# Processor.net
KiCad netlist of a schematic drawn in Altium Designer
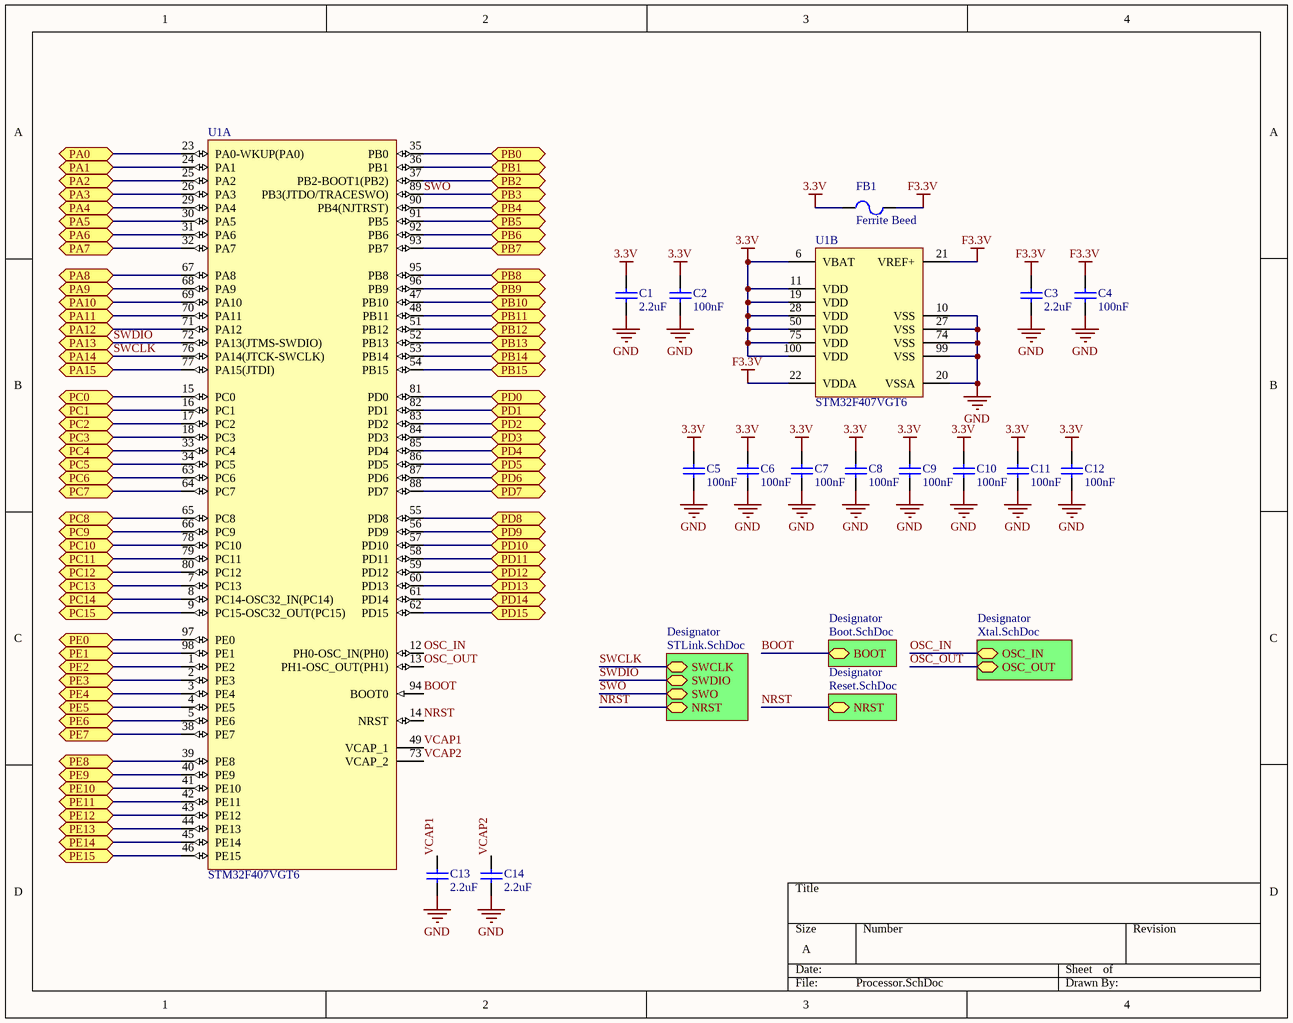
[diagram p0: Processor.SchDoc]

(export (version "E")
  (design (tool "Eeschema 10.0.6"))
  (components
    (comp (ref "C1")
      (value "2.2uF")
      (footprint "2012[0805]")
      (description "Capacitor")
      (fields (field (name "Comment") "Cap_UP") (field (name "PUBLISHER") "Altium Limited"))
      (libsource (lib "KN2CLib") (part "Cap_UP"))
    )
    (comp (ref "C2")
      (value "100nF")
      (footprint "2012[0805]")
      (description "Capacitor")
      (fields (field (name "Comment") "Cap_UP") (field (name "PUBLISHER") "Altium Limited"))
      (libsource (lib "KN2CLib") (part "Cap_UP"))
    )
    (comp (ref "C3")
      (value "2.2uF")
      (footprint "2012[0805]")
      (description "Capacitor")
      (fields (field (name "Comment") "Cap_UP") (field (name "PUBLISHER") "Altium Limited"))
      (libsource (lib "KN2CLib") (part "Cap_UP"))
    )
    (comp (ref "C4")
      (value "100nF")
      (footprint "2012[0805]")
      (description "Capacitor")
      (fields (field (name "Comment") "Cap_UP") (field (name "PUBLISHER") "Altium Limited"))
      (libsource (lib "KN2CLib") (part "Cap_UP"))
    )
    (comp (ref "C5")
      (value "100nF")
      (footprint "2012[0805]")
      (description "Capacitor")
      (fields (field (name "Comment") "Cap_UP") (field (name "PUBLISHER") "Altium Limited"))
      (libsource (lib "KN2CLib") (part "Cap_UP"))
    )
    (comp (ref "C6")
      (value "100nF")
      (footprint "2012[0805]")
      (description "Capacitor")
      (fields (field (name "Comment") "Cap_UP") (field (name "PUBLISHER") "Altium Limited"))
      (libsource (lib "KN2CLib") (part "Cap_UP"))
    )
    (comp (ref "C7")
      (value "100nF")
      (footprint "2012[0805]")
      (description "Capacitor")
      (fields (field (name "Comment") "Cap_UP") (field (name "PUBLISHER") "Altium Limited"))
      (libsource (lib "KN2CLib") (part "Cap_UP"))
    )
    (comp (ref "C8")
      (value "100nF")
      (footprint "2012[0805]")
      (description "Capacitor")
      (fields (field (name "Comment") "Cap_UP") (field (name "PUBLISHER") "Altium Limited"))
      (libsource (lib "KN2CLib") (part "Cap_UP"))
    )
    (comp (ref "C9")
      (value "100nF")
      (footprint "2012[0805]")
      (description "Capacitor")
      (fields (field (name "Comment") "Cap_UP") (field (name "PUBLISHER") "Altium Limited"))
      (libsource (lib "KN2CLib") (part "Cap_UP"))
    )
    (comp (ref "C10")
      (value "100nF")
      (footprint "2012[0805]")
      (description "Capacitor")
      (fields (field (name "Comment") "Cap_UP") (field (name "PUBLISHER") "Altium Limited"))
      (libsource (lib "KN2CLib") (part "Cap_UP"))
    )
    (comp (ref "C11")
      (value "100nF")
      (footprint "2012[0805]")
      (description "Capacitor")
      (fields (field (name "Comment") "Cap_UP") (field (name "PUBLISHER") "Altium Limited"))
      (libsource (lib "KN2CLib") (part "Cap_UP"))
    )
    (comp (ref "C12")
      (value "100nF")
      (footprint "2012[0805]")
      (description "Capacitor")
      (fields (field (name "Comment") "Cap_UP") (field (name "PUBLISHER") "Altium Limited"))
      (libsource (lib "KN2CLib") (part "Cap_UP"))
    )
    (comp (ref "C13")
      (value "2.2uF")
      (footprint "2012[0805]")
      (description "Capacitor")
      (fields (field (name "Comment") "Cap_UP") (field (name "PUBLISHER") "Altium Limited"))
      (libsource (lib "KN2CLib") (part "Cap_UP"))
    )
    (comp (ref "C14")
      (value "2.2uF")
      (footprint "2012[0805]")
      (description "Capacitor")
      (fields (field (name "Comment") "Cap_UP") (field (name "PUBLISHER") "Altium Limited"))
      (libsource (lib "KN2CLib") (part "Cap_UP"))
    )
    (comp (ref "FB1")
      (value "Ferrite Beed")
      (footprint "3216[1206]")
      (fields (field (name "PUBLISHER") "Altium Limited"))
      (libsource (lib "KN2CLib") (part "Ferrite Beed"))
    )
    (comp (ref "U1")
      (value "STM32F407VGT6")
      (footprint "STM-LQFP100_N")
      (fields (field (name "MANUFACTURER") "STMicroelectronics"))
      (libsource (lib "STMicroelectronics STM32 F4") (part "STM32F407VGT6"))
    )
  )
  (nets
    (net (code "1") (name "/BOOT") (class "Default")
      (node (ref "U1") (pin "94") (pinfunction "BOOT0_94") (pintype "input"))
    )
    (net (code "2") (name "/NRST") (class "Default")
      (node (ref "U1") (pin "14") (pinfunction "NRST_14") (pintype "bidirectional"))
    )
    (net (code "3") (name "/OSC_IN") (class "Default")
      (node (ref "U1") (pin "12") (pinfunction "PH0-OSC_IN(PH0)_12") (pintype "bidirectional"))
    )
    (net (code "4") (name "/OSC_OUT") (class "Default")
      (node (ref "U1") (pin "13") (pinfunction "PH1-OSC_OUT(PH1)_13") (pintype "bidirectional"))
    )
    (net (code "5") (name "/PA0") (class "Default")
      (node (ref "U1") (pin "23") (pinfunction "PA0-WKUP(PA0)_23") (pintype "bidirectional"))
    )
    (net (code "6") (name "/PA1") (class "Default")
      (node (ref "U1") (pin "24") (pinfunction "PA1_24") (pintype "bidirectional"))
    )
    (net (code "7") (name "/PA2") (class "Default")
      (node (ref "U1") (pin "25") (pinfunction "PA2_25") (pintype "bidirectional"))
    )
    (net (code "8") (name "/PA3") (class "Default")
      (node (ref "U1") (pin "26") (pinfunction "PA3_26") (pintype "bidirectional"))
    )
    (net (code "9") (name "/PA4") (class "Default")
      (node (ref "U1") (pin "29") (pinfunction "PA4_29") (pintype "bidirectional"))
    )
    (net (code "10") (name "/PA5") (class "Default")
      (node (ref "U1") (pin "30") (pinfunction "PA5_30") (pintype "bidirectional"))
    )
    (net (code "11") (name "/PA6") (class "Default")
      (node (ref "U1") (pin "31") (pinfunction "PA6_31") (pintype "bidirectional"))
    )
    (net (code "12") (name "/PA7") (class "Default")
      (node (ref "U1") (pin "32") (pinfunction "PA7_32") (pintype "bidirectional"))
    )
    (net (code "13") (name "/PA8") (class "Default")
      (node (ref "U1") (pin "67") (pinfunction "PA8_67") (pintype "bidirectional"))
    )
    (net (code "14") (name "/PA9") (class "Default")
      (node (ref "U1") (pin "68") (pinfunction "PA9_68") (pintype "bidirectional"))
    )
    (net (code "15") (name "/PA10") (class "Default")
      (node (ref "U1") (pin "69") (pinfunction "PA10_69") (pintype "bidirectional"))
    )
    (net (code "16") (name "/PA11") (class "Default")
      (node (ref "U1") (pin "70") (pinfunction "PA11_70") (pintype "bidirectional"))
    )
    (net (code "17") (name "/PA12") (class "Default")
      (node (ref "U1") (pin "71") (pinfunction "PA12_71") (pintype "bidirectional"))
    )
    (net (code "18") (name "/PA15") (class "Default")
      (node (ref "U1") (pin "77") (pinfunction "PA15(JTDI)_77") (pintype "bidirectional"))
    )
    (net (code "19") (name "/PB0") (class "Default")
      (node (ref "U1") (pin "35") (pinfunction "PB0_35") (pintype "bidirectional"))
    )
    (net (code "20") (name "/PB1") (class "Default")
      (node (ref "U1") (pin "36") (pinfunction "PB1_36") (pintype "bidirectional"))
    )
    (net (code "21") (name "/PB2") (class "Default")
      (node (ref "U1") (pin "37") (pinfunction "PB2-BOOT1(PB2)_37") (pintype "bidirectional"))
    )
    (net (code "22") (name "/PB4") (class "Default")
      (node (ref "U1") (pin "90") (pinfunction "PB4(NJTRST)_90") (pintype "bidirectional"))
    )
    (net (code "23") (name "/PB5") (class "Default")
      (node (ref "U1") (pin "91") (pinfunction "PB5_91") (pintype "bidirectional"))
    )
    (net (code "24") (name "/PB6") (class "Default")
      (node (ref "U1") (pin "92") (pinfunction "PB6_92") (pintype "bidirectional"))
    )
    (net (code "25") (name "/PB7") (class "Default")
      (node (ref "U1") (pin "93") (pinfunction "PB7_93") (pintype "bidirectional"))
    )
    (net (code "26") (name "/PB8") (class "Default")
      (node (ref "U1") (pin "95") (pinfunction "PB8_95") (pintype "bidirectional"))
    )
    (net (code "27") (name "/PB9") (class "Default")
      (node (ref "U1") (pin "96") (pinfunction "PB9_96") (pintype "bidirectional"))
    )
    (net (code "28") (name "/PB10") (class "Default")
      (node (ref "U1") (pin "47") (pinfunction "PB10_47") (pintype "bidirectional"))
    )
    (net (code "29") (name "/PB11") (class "Default")
      (node (ref "U1") (pin "48") (pinfunction "PB11_48") (pintype "bidirectional"))
    )
    (net (code "30") (name "/PB12") (class "Default")
      (node (ref "U1") (pin "51") (pinfunction "PB12_51") (pintype "bidirectional"))
    )
    (net (code "31") (name "/PB13") (class "Default")
      (node (ref "U1") (pin "52") (pinfunction "PB13_52") (pintype "bidirectional"))
    )
    (net (code "32") (name "/PB14") (class "Default")
      (node (ref "U1") (pin "53") (pinfunction "PB14_53") (pintype "bidirectional"))
    )
    (net (code "33") (name "/PB15") (class "Default")
      (node (ref "U1") (pin "54") (pinfunction "PB15_54") (pintype "bidirectional"))
    )
    (net (code "34") (name "/PC0") (class "Default")
      (node (ref "U1") (pin "15") (pinfunction "PC0_15") (pintype "bidirectional"))
    )
    (net (code "35") (name "/PC1") (class "Default")
      (node (ref "U1") (pin "16") (pinfunction "PC1_16") (pintype "bidirectional"))
    )
    (net (code "36") (name "/PC2") (class "Default")
      (node (ref "U1") (pin "17") (pinfunction "PC2_17") (pintype "bidirectional"))
    )
    (net (code "37") (name "/PC3") (class "Default")
      (node (ref "U1") (pin "18") (pinfunction "PC3_18") (pintype "bidirectional"))
    )
    (net (code "38") (name "/PC4") (class "Default")
      (node (ref "U1") (pin "33") (pinfunction "PC4_33") (pintype "bidirectional"))
    )
    (net (code "39") (name "/PC5") (class "Default")
      (node (ref "U1") (pin "34") (pinfunction "PC5_34") (pintype "bidirectional"))
    )
    (net (code "40") (name "/PC6") (class "Default")
      (node (ref "U1") (pin "63") (pinfunction "PC6_63") (pintype "bidirectional"))
    )
    (net (code "41") (name "/PC7") (class "Default")
      (node (ref "U1") (pin "64") (pinfunction "PC7_64") (pintype "bidirectional"))
    )
    (net (code "42") (name "/PC8") (class "Default")
      (node (ref "U1") (pin "65") (pinfunction "PC8_65") (pintype "bidirectional"))
    )
    (net (code "43") (name "/PC9") (class "Default")
      (node (ref "U1") (pin "66") (pinfunction "PC9_66") (pintype "bidirectional"))
    )
    (net (code "44") (name "/PC10") (class "Default")
      (node (ref "U1") (pin "78") (pinfunction "PC10_78") (pintype "bidirectional"))
    )
    (net (code "45") (name "/PC11") (class "Default")
      (node (ref "U1") (pin "79") (pinfunction "PC11_79") (pintype "bidirectional"))
    )
    (net (code "46") (name "/PC12") (class "Default")
      (node (ref "U1") (pin "80") (pinfunction "PC12_80") (pintype "bidirectional"))
    )
    (net (code "47") (name "/PC13") (class "Default")
      (node (ref "U1") (pin "7") (pinfunction "PC13_7") (pintype "bidirectional"))
    )
    (net (code "48") (name "/PC14") (class "Default")
      (node (ref "U1") (pin "8") (pinfunction "PC14-OSC32_IN(PC14)_8") (pintype "bidirectional"))
    )
    (net (code "49") (name "/PC15") (class "Default")
      (node (ref "U1") (pin "9") (pinfunction "PC15-OSC32_OUT(PC15)_9") (pintype "bidirectional"))
    )
    (net (code "50") (name "/PD0") (class "Default")
      (node (ref "U1") (pin "81") (pinfunction "PD0_81") (pintype "bidirectional"))
    )
    (net (code "51") (name "/PD1") (class "Default")
      (node (ref "U1") (pin "82") (pinfunction "PD1_82") (pintype "bidirectional"))
    )
    (net (code "52") (name "/PD2") (class "Default")
      (node (ref "U1") (pin "83") (pinfunction "PD2_83") (pintype "bidirectional"))
    )
    (net (code "53") (name "/PD3") (class "Default")
      (node (ref "U1") (pin "84") (pinfunction "PD3_84") (pintype "bidirectional"))
    )
    (net (code "54") (name "/PD4") (class "Default")
      (node (ref "U1") (pin "85") (pinfunction "PD4_85") (pintype "bidirectional"))
    )
    (net (code "55") (name "/PD5") (class "Default")
      (node (ref "U1") (pin "86") (pinfunction "PD5_86") (pintype "bidirectional"))
    )
    (net (code "56") (name "/PD6") (class "Default")
      (node (ref "U1") (pin "87") (pinfunction "PD6_87") (pintype "bidirectional"))
    )
    (net (code "57") (name "/PD7") (class "Default")
      (node (ref "U1") (pin "88") (pinfunction "PD7_88") (pintype "bidirectional"))
    )
    (net (code "58") (name "/PD8") (class "Default")
      (node (ref "U1") (pin "55") (pinfunction "PD8_55") (pintype "bidirectional"))
    )
    (net (code "59") (name "/PD9") (class "Default")
      (node (ref "U1") (pin "56") (pinfunction "PD9_56") (pintype "bidirectional"))
    )
    (net (code "60") (name "/PD10") (class "Default")
      (node (ref "U1") (pin "57") (pinfunction "PD10_57") (pintype "bidirectional"))
    )
    (net (code "61") (name "/PD11") (class "Default")
      (node (ref "U1") (pin "58") (pinfunction "PD11_58") (pintype "bidirectional"))
    )
    (net (code "62") (name "/PD12") (class "Default")
      (node (ref "U1") (pin "59") (pinfunction "PD12_59") (pintype "bidirectional"))
    )
    (net (code "63") (name "/PD13") (class "Default")
      (node (ref "U1") (pin "60") (pinfunction "PD13_60") (pintype "bidirectional"))
    )
    (net (code "64") (name "/PD14") (class "Default")
      (node (ref "U1") (pin "61") (pinfunction "PD14_61") (pintype "bidirectional"))
    )
    (net (code "65") (name "/PD15") (class "Default")
      (node (ref "U1") (pin "62") (pinfunction "PD15_62") (pintype "bidirectional"))
    )
    (net (code "66") (name "/PE0") (class "Default")
      (node (ref "U1") (pin "97") (pinfunction "PE0_97") (pintype "bidirectional"))
    )
    (net (code "67") (name "/PE1") (class "Default")
      (node (ref "U1") (pin "98") (pinfunction "PE1_98") (pintype "bidirectional"))
    )
    (net (code "68") (name "/PE2") (class "Default")
      (node (ref "U1") (pin "1") (pinfunction "PE2_1") (pintype "bidirectional"))
    )
    (net (code "69") (name "/PE3") (class "Default")
      (node (ref "U1") (pin "2") (pinfunction "PE3_2") (pintype "bidirectional"))
    )
    (net (code "70") (name "/PE4") (class "Default")
      (node (ref "U1") (pin "3") (pinfunction "PE4_3") (pintype "bidirectional"))
    )
    (net (code "71") (name "/PE5") (class "Default")
      (node (ref "U1") (pin "4") (pinfunction "PE5_4") (pintype "bidirectional"))
    )
    (net (code "72") (name "/PE6") (class "Default")
      (node (ref "U1") (pin "5") (pinfunction "PE6_5") (pintype "bidirectional"))
    )
    (net (code "73") (name "/PE7") (class "Default")
      (node (ref "U1") (pin "38") (pinfunction "PE7_38") (pintype "bidirectional"))
    )
    (net (code "74") (name "/PE8") (class "Default")
      (node (ref "U1") (pin "39") (pinfunction "PE8_39") (pintype "bidirectional"))
    )
    (net (code "75") (name "/PE9") (class "Default")
      (node (ref "U1") (pin "40") (pinfunction "PE9_40") (pintype "bidirectional"))
    )
    (net (code "76") (name "/PE10") (class "Default")
      (node (ref "U1") (pin "41") (pinfunction "PE10_41") (pintype "bidirectional"))
    )
    (net (code "77") (name "/PE11") (class "Default")
      (node (ref "U1") (pin "42") (pinfunction "PE11_42") (pintype "bidirectional"))
    )
    (net (code "78") (name "/PE12") (class "Default")
      (node (ref "U1") (pin "43") (pinfunction "PE12_43") (pintype "bidirectional"))
    )
    (net (code "79") (name "/PE13") (class "Default")
      (node (ref "U1") (pin "44") (pinfunction "PE13_44") (pintype "bidirectional"))
    )
    (net (code "80") (name "/PE14") (class "Default")
      (node (ref "U1") (pin "45") (pinfunction "PE14_45") (pintype "bidirectional"))
    )
    (net (code "81") (name "/PE15") (class "Default")
      (node (ref "U1") (pin "46") (pinfunction "PE15_46") (pintype "bidirectional"))
    )
    (net (code "82") (name "/SWCLK") (class "Default")
      (node (ref "U1") (pin "76") (pinfunction "PA14(JTCK-SWCLK)_76") (pintype "bidirectional"))
    )
    (net (code "83") (name "/SWDIO") (class "Default")
      (node (ref "U1") (pin "72") (pinfunction "PA13(JTMS-SWDIO)_72") (pintype "bidirectional"))
    )
    (net (code "84") (name "/SWO") (class "Default")
      (node (ref "U1") (pin "89") (pinfunction "PB3(JTDO/TRACESWO)_89") (pintype "bidirectional"))
    )
    (net (code "85") (name "/VCAP1") (class "Default")
      (node (ref "C13") (pin "2") (pinfunction "2_2") (pintype "passive"))
      (node (ref "U1") (pin "49") (pinfunction "VCAP_1_49") (pintype "power_in"))
    )
    (net (code "86") (name "/VCAP2") (class "Default")
      (node (ref "C14") (pin "2") (pinfunction "2_2") (pintype "passive"))
      (node (ref "U1") (pin "73") (pinfunction "VCAP_2_73") (pintype "power_in"))
    )
    (net (code "87") (name "3.3V") (class "Default")
      (node (ref "C1") (pin "2") (pinfunction "2_2") (pintype "passive"))
      (node (ref "C10") (pin "2") (pinfunction "2_2") (pintype "passive"))
      (node (ref "C11") (pin "2") (pinfunction "2_2") (pintype "passive"))
      (node (ref "C12") (pin "2") (pinfunction "2_2") (pintype "passive"))
      (node (ref "C2") (pin "2") (pinfunction "2_2") (pintype "passive"))
      (node (ref "C5") (pin "2") (pinfunction "2_2") (pintype "passive"))
      (node (ref "C6") (pin "2") (pinfunction "2_2") (pintype "passive"))
      (node (ref "C7") (pin "2") (pinfunction "2_2") (pintype "passive"))
      (node (ref "C8") (pin "2") (pinfunction "2_2") (pintype "passive"))
      (node (ref "C9") (pin "2") (pinfunction "2_2") (pintype "passive"))
      (node (ref "FB1") (pin "1") (pinfunction "1_1") (pintype "passive"))
      (node (ref "U1") (pin "100") (pinfunction "VDD_100") (pintype "power_in"))
      (node (ref "U1") (pin "11") (pinfunction "VDD_11") (pintype "power_in"))
      (node (ref "U1") (pin "19") (pinfunction "VDD_19") (pintype "power_in"))
      (node (ref "U1") (pin "28") (pinfunction "VDD_28") (pintype "power_in"))
      (node (ref "U1") (pin "50") (pinfunction "VDD_50") (pintype "power_in"))
      (node (ref "U1") (pin "6") (pinfunction "VBAT_6") (pintype "power_in"))
      (node (ref "U1") (pin "75") (pinfunction "VDD_75") (pintype "power_in"))
    )
    (net (code "88") (name "F3.3V") (class "Default")
      (node (ref "C3") (pin "2") (pinfunction "2_2") (pintype "passive"))
      (node (ref "C4") (pin "2") (pinfunction "2_2") (pintype "passive"))
      (node (ref "FB1") (pin "2") (pinfunction "2_2") (pintype "passive"))
      (node (ref "U1") (pin "21") (pinfunction "VREF+_21") (pintype "power_in"))
      (node (ref "U1") (pin "22") (pinfunction "VDDA_22") (pintype "power_in"))
    )
    (net (code "89") (name "GND") (class "Default")
      (node (ref "C1") (pin "1") (pinfunction "1_1") (pintype "passive"))
      (node (ref "C10") (pin "1") (pinfunction "1_1") (pintype "passive"))
      (node (ref "C11") (pin "1") (pinfunction "1_1") (pintype "passive"))
      (node (ref "C12") (pin "1") (pinfunction "1_1") (pintype "passive"))
      (node (ref "C13") (pin "1") (pinfunction "1_1") (pintype "passive"))
      (node (ref "C14") (pin "1") (pinfunction "1_1") (pintype "passive"))
      (node (ref "C2") (pin "1") (pinfunction "1_1") (pintype "passive"))
      (node (ref "C3") (pin "1") (pinfunction "1_1") (pintype "passive"))
      (node (ref "C4") (pin "1") (pinfunction "1_1") (pintype "passive"))
      (node (ref "C5") (pin "1") (pinfunction "1_1") (pintype "passive"))
      (node (ref "C6") (pin "1") (pinfunction "1_1") (pintype "passive"))
      (node (ref "C7") (pin "1") (pinfunction "1_1") (pintype "passive"))
      (node (ref "C8") (pin "1") (pinfunction "1_1") (pintype "passive"))
      (node (ref "C9") (pin "1") (pinfunction "1_1") (pintype "passive"))
      (node (ref "U1") (pin "10") (pinfunction "VSS_10") (pintype "power_in"))
      (node (ref "U1") (pin "20") (pinfunction "VSSA_20") (pintype "power_in"))
      (node (ref "U1") (pin "27") (pinfunction "VSS_27") (pintype "power_in"))
      (node (ref "U1") (pin "74") (pinfunction "VSS_74") (pintype "power_in"))
      (node (ref "U1") (pin "99") (pinfunction "VSS_99") (pintype "power_in"))
    )
  )
)
